# Tach-to-CAN.net
KiCad netlist of a schematic drawn in EAGLE
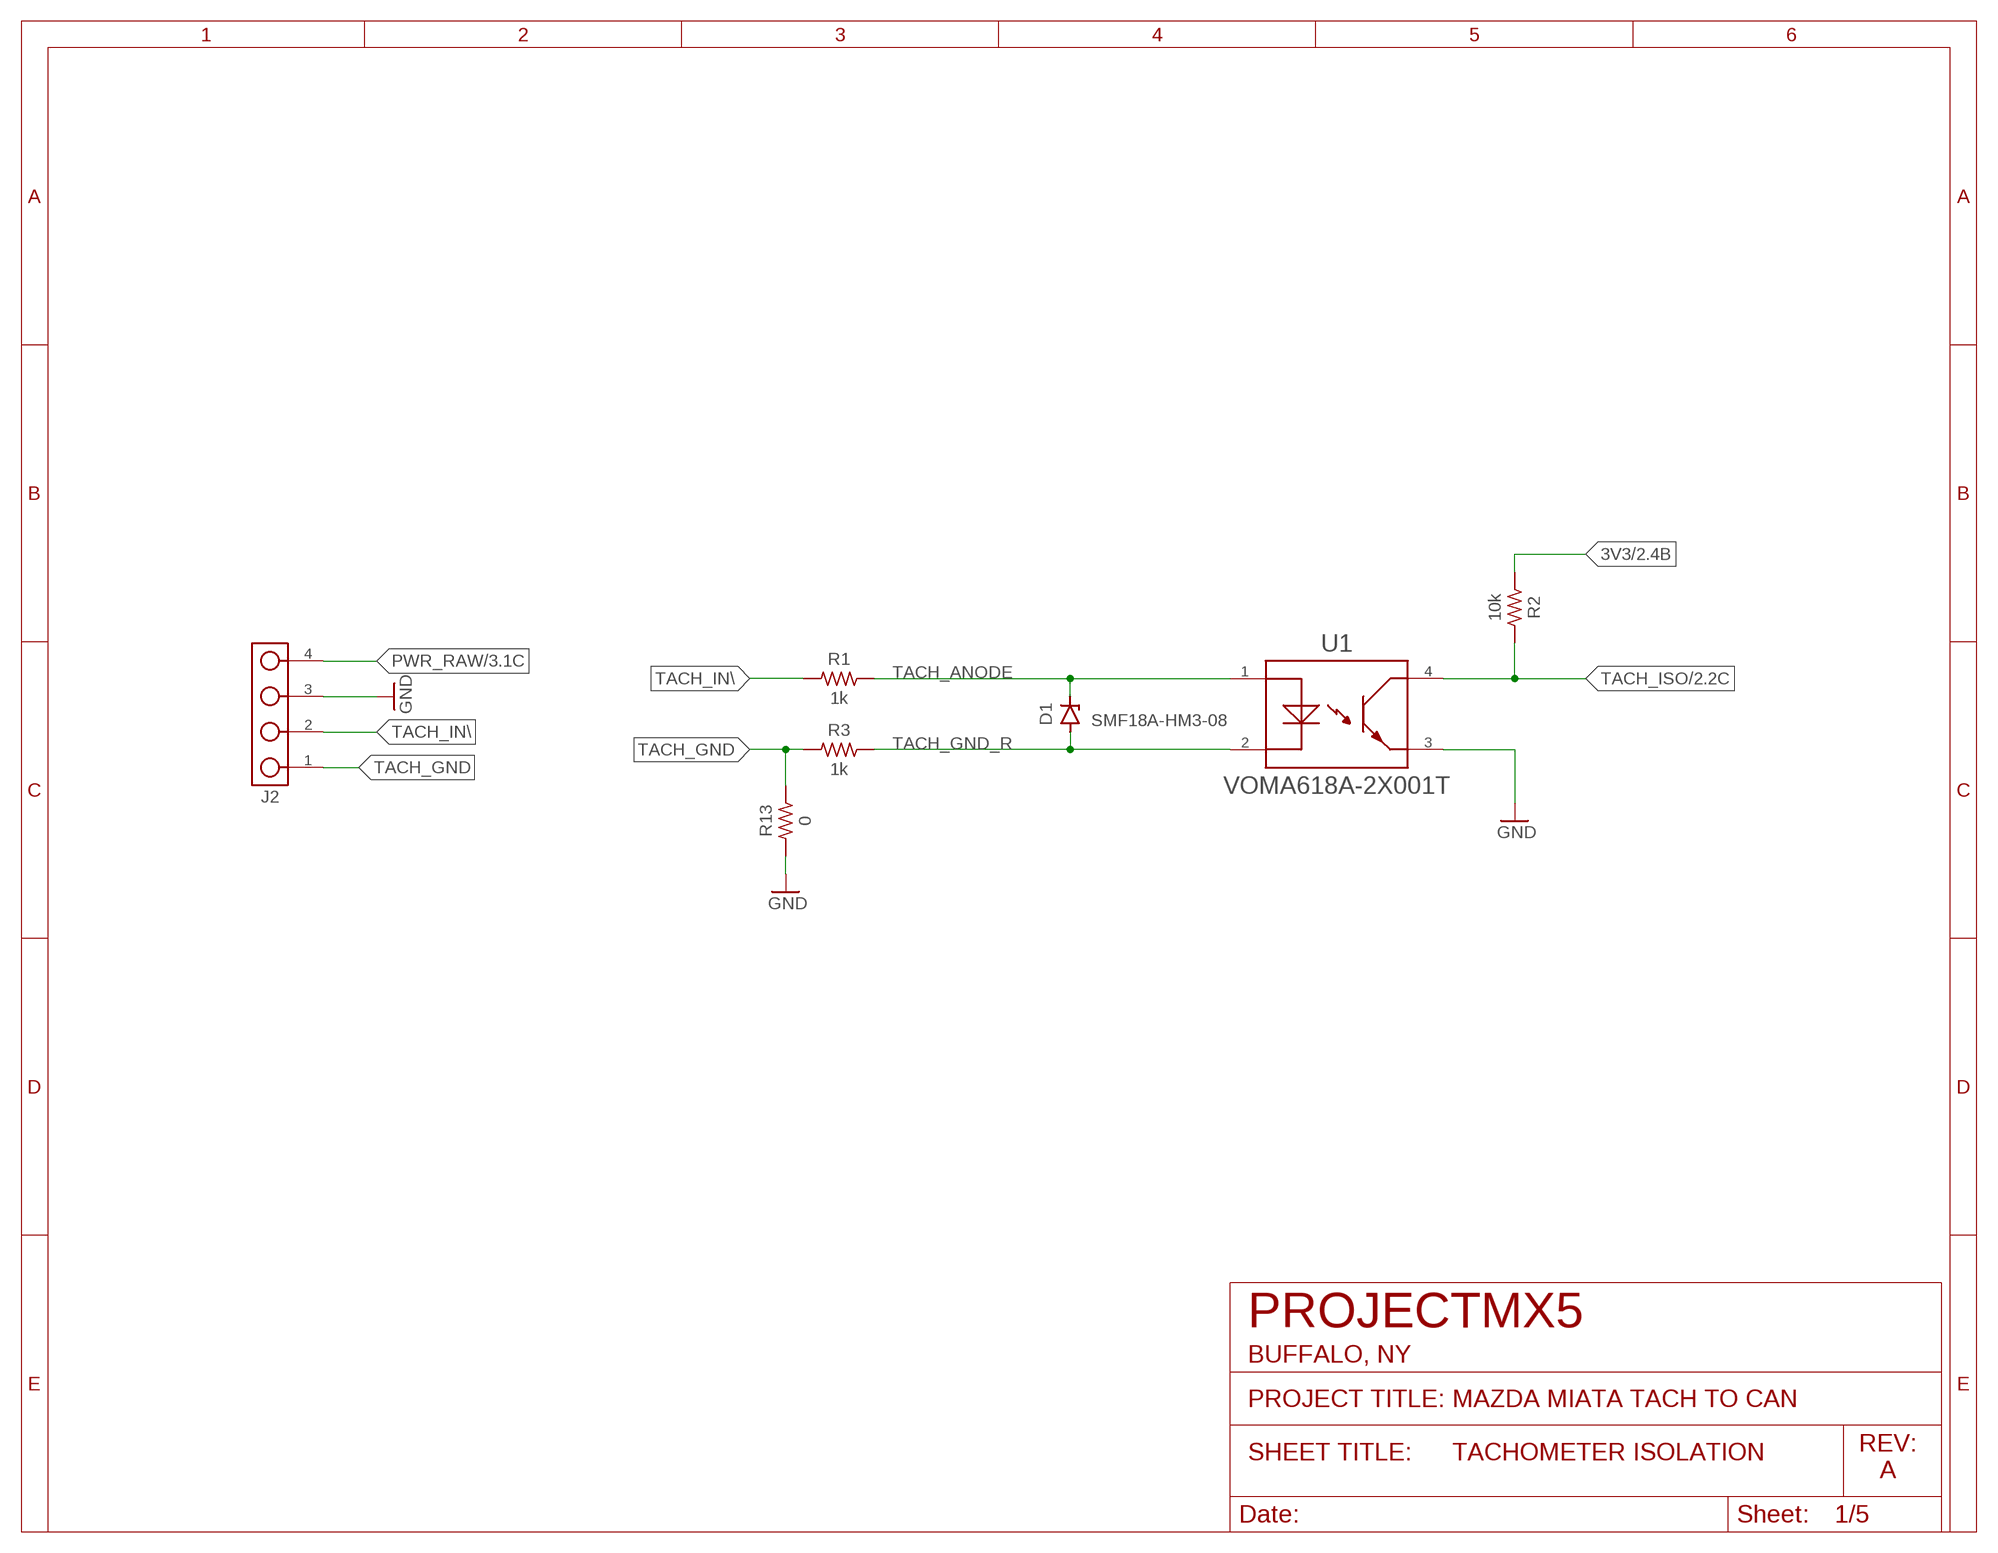
[diagram p0: schematic, sheet 1]
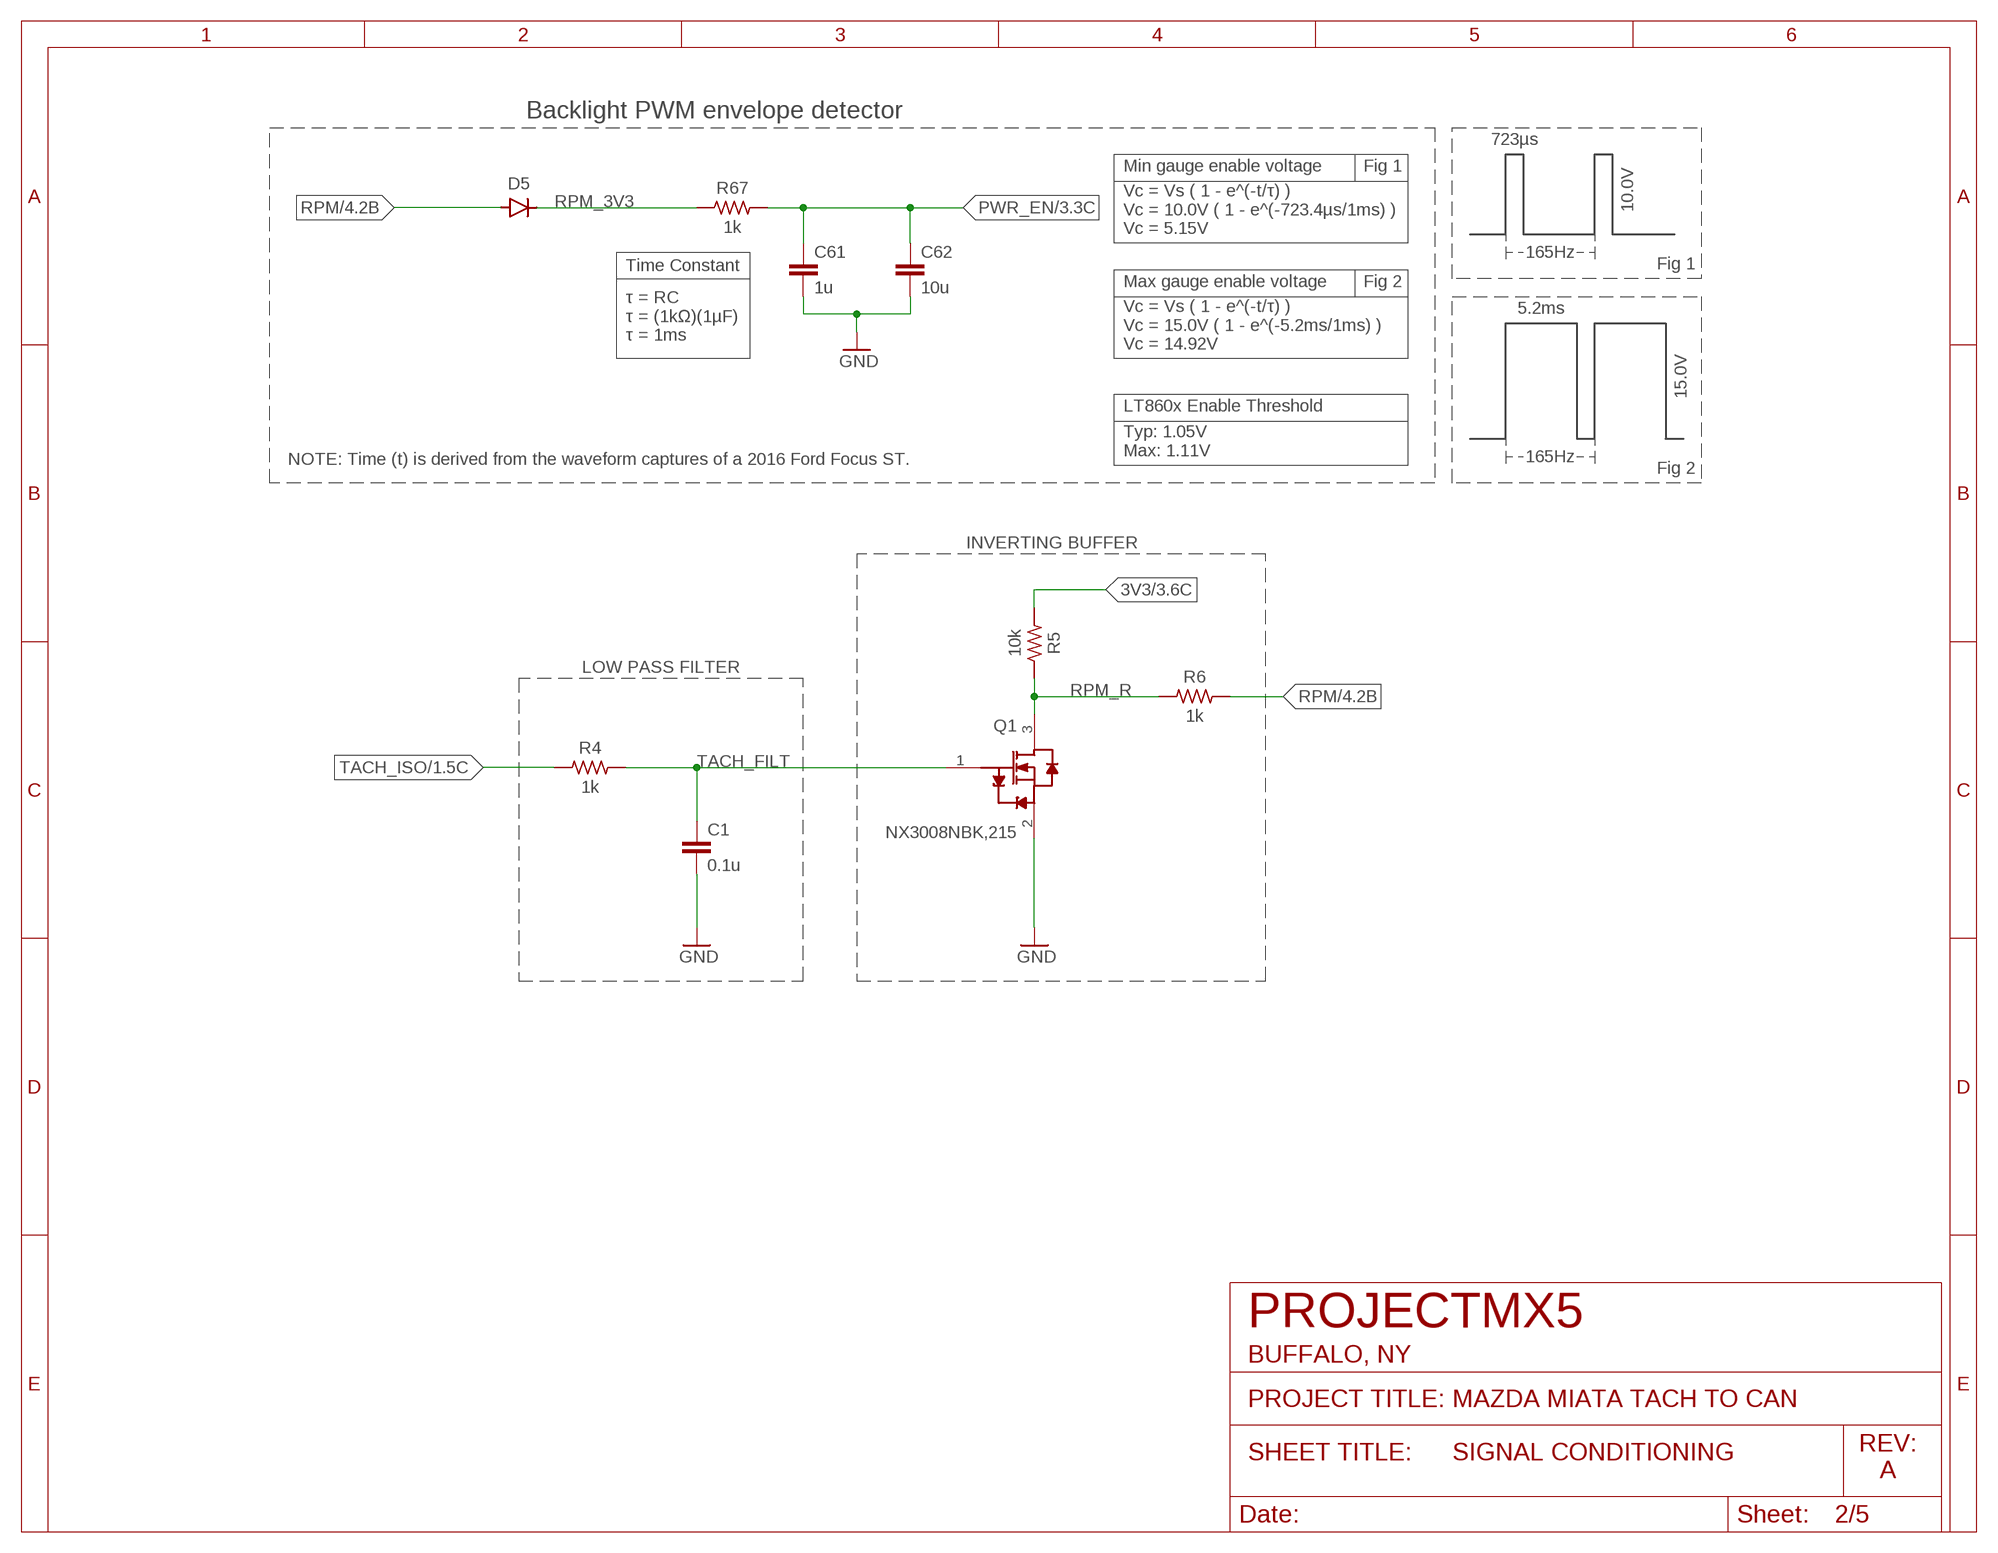
[diagram p1: schematic, sheet 2]
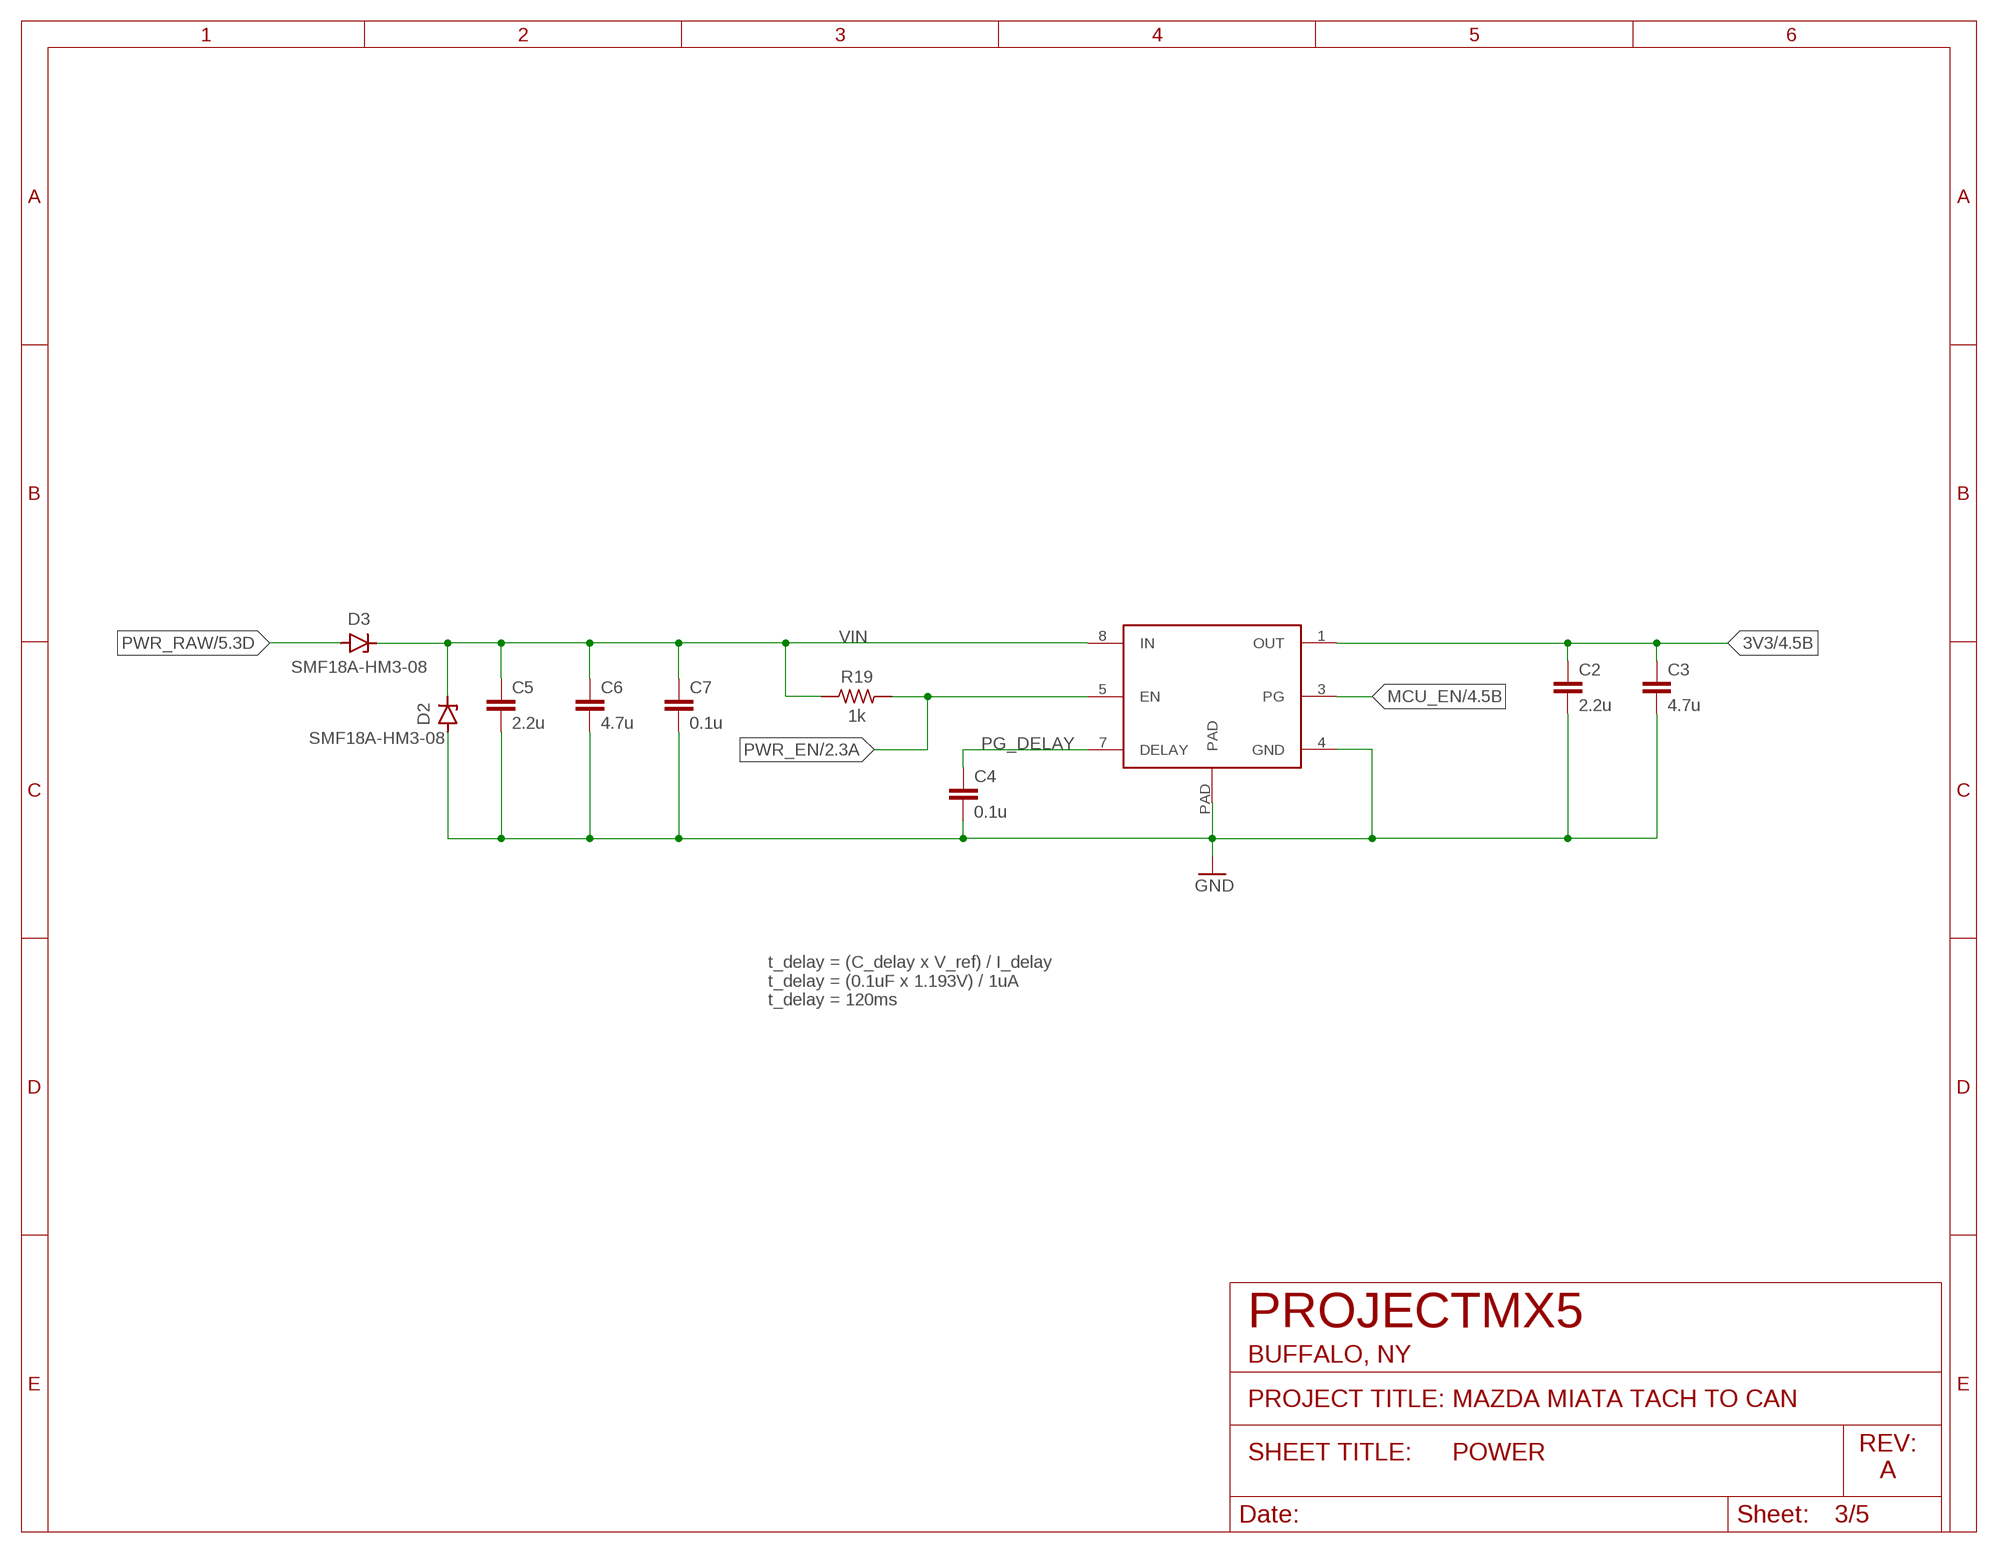
[diagram p2: schematic, sheet 3]
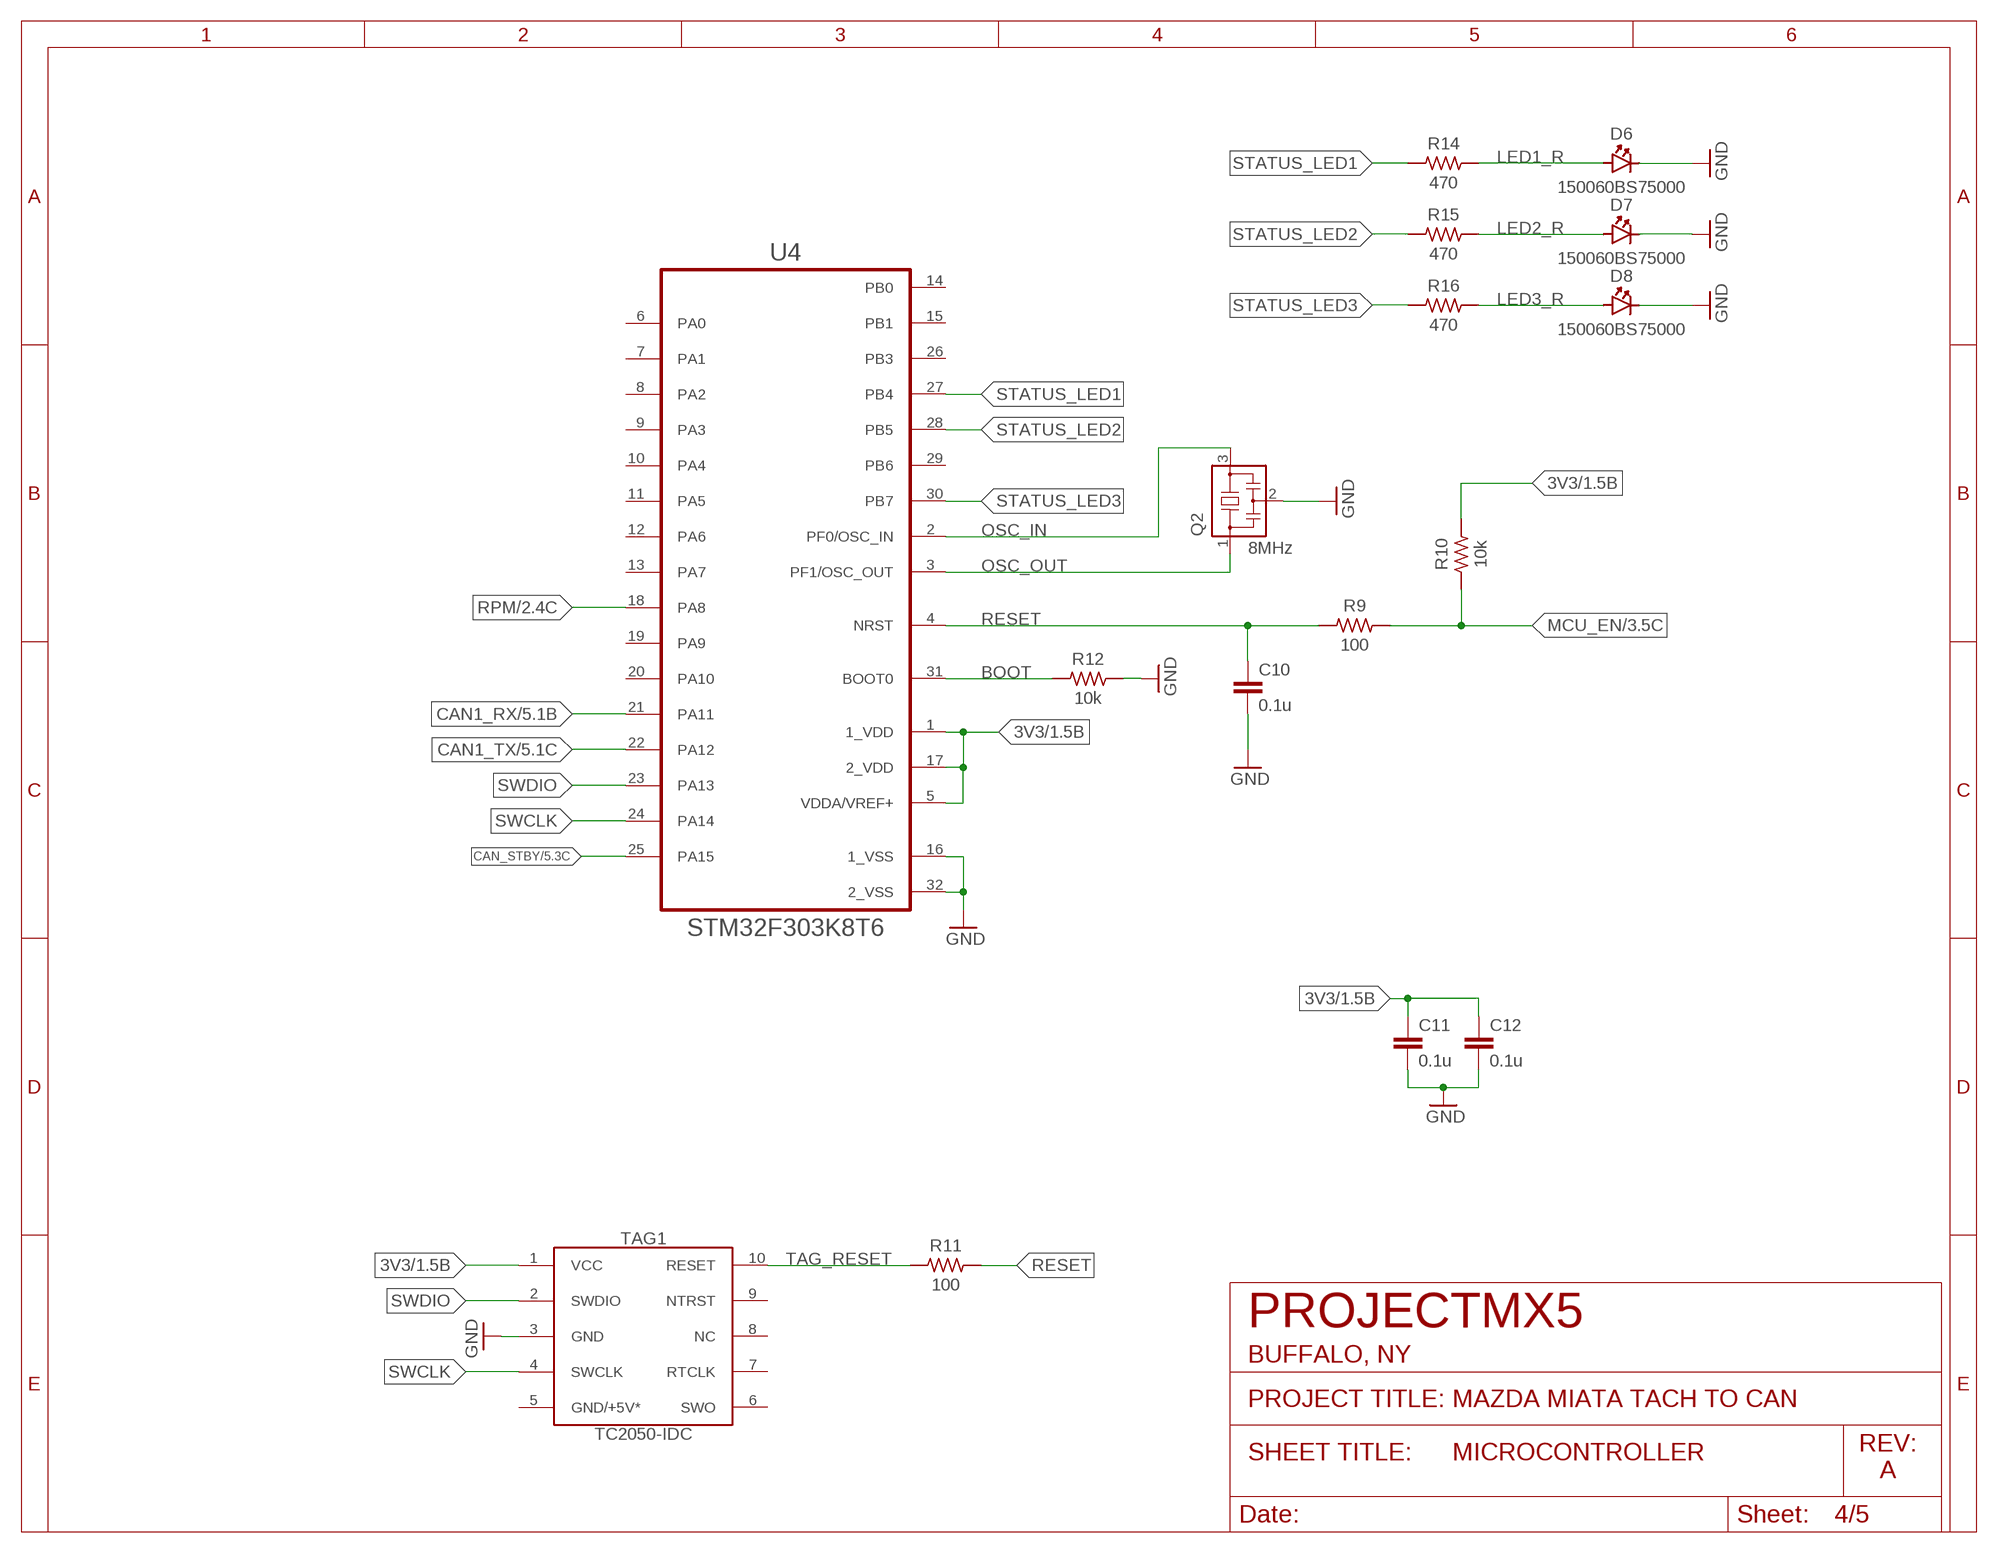
[diagram p3: schematic, sheet 4]
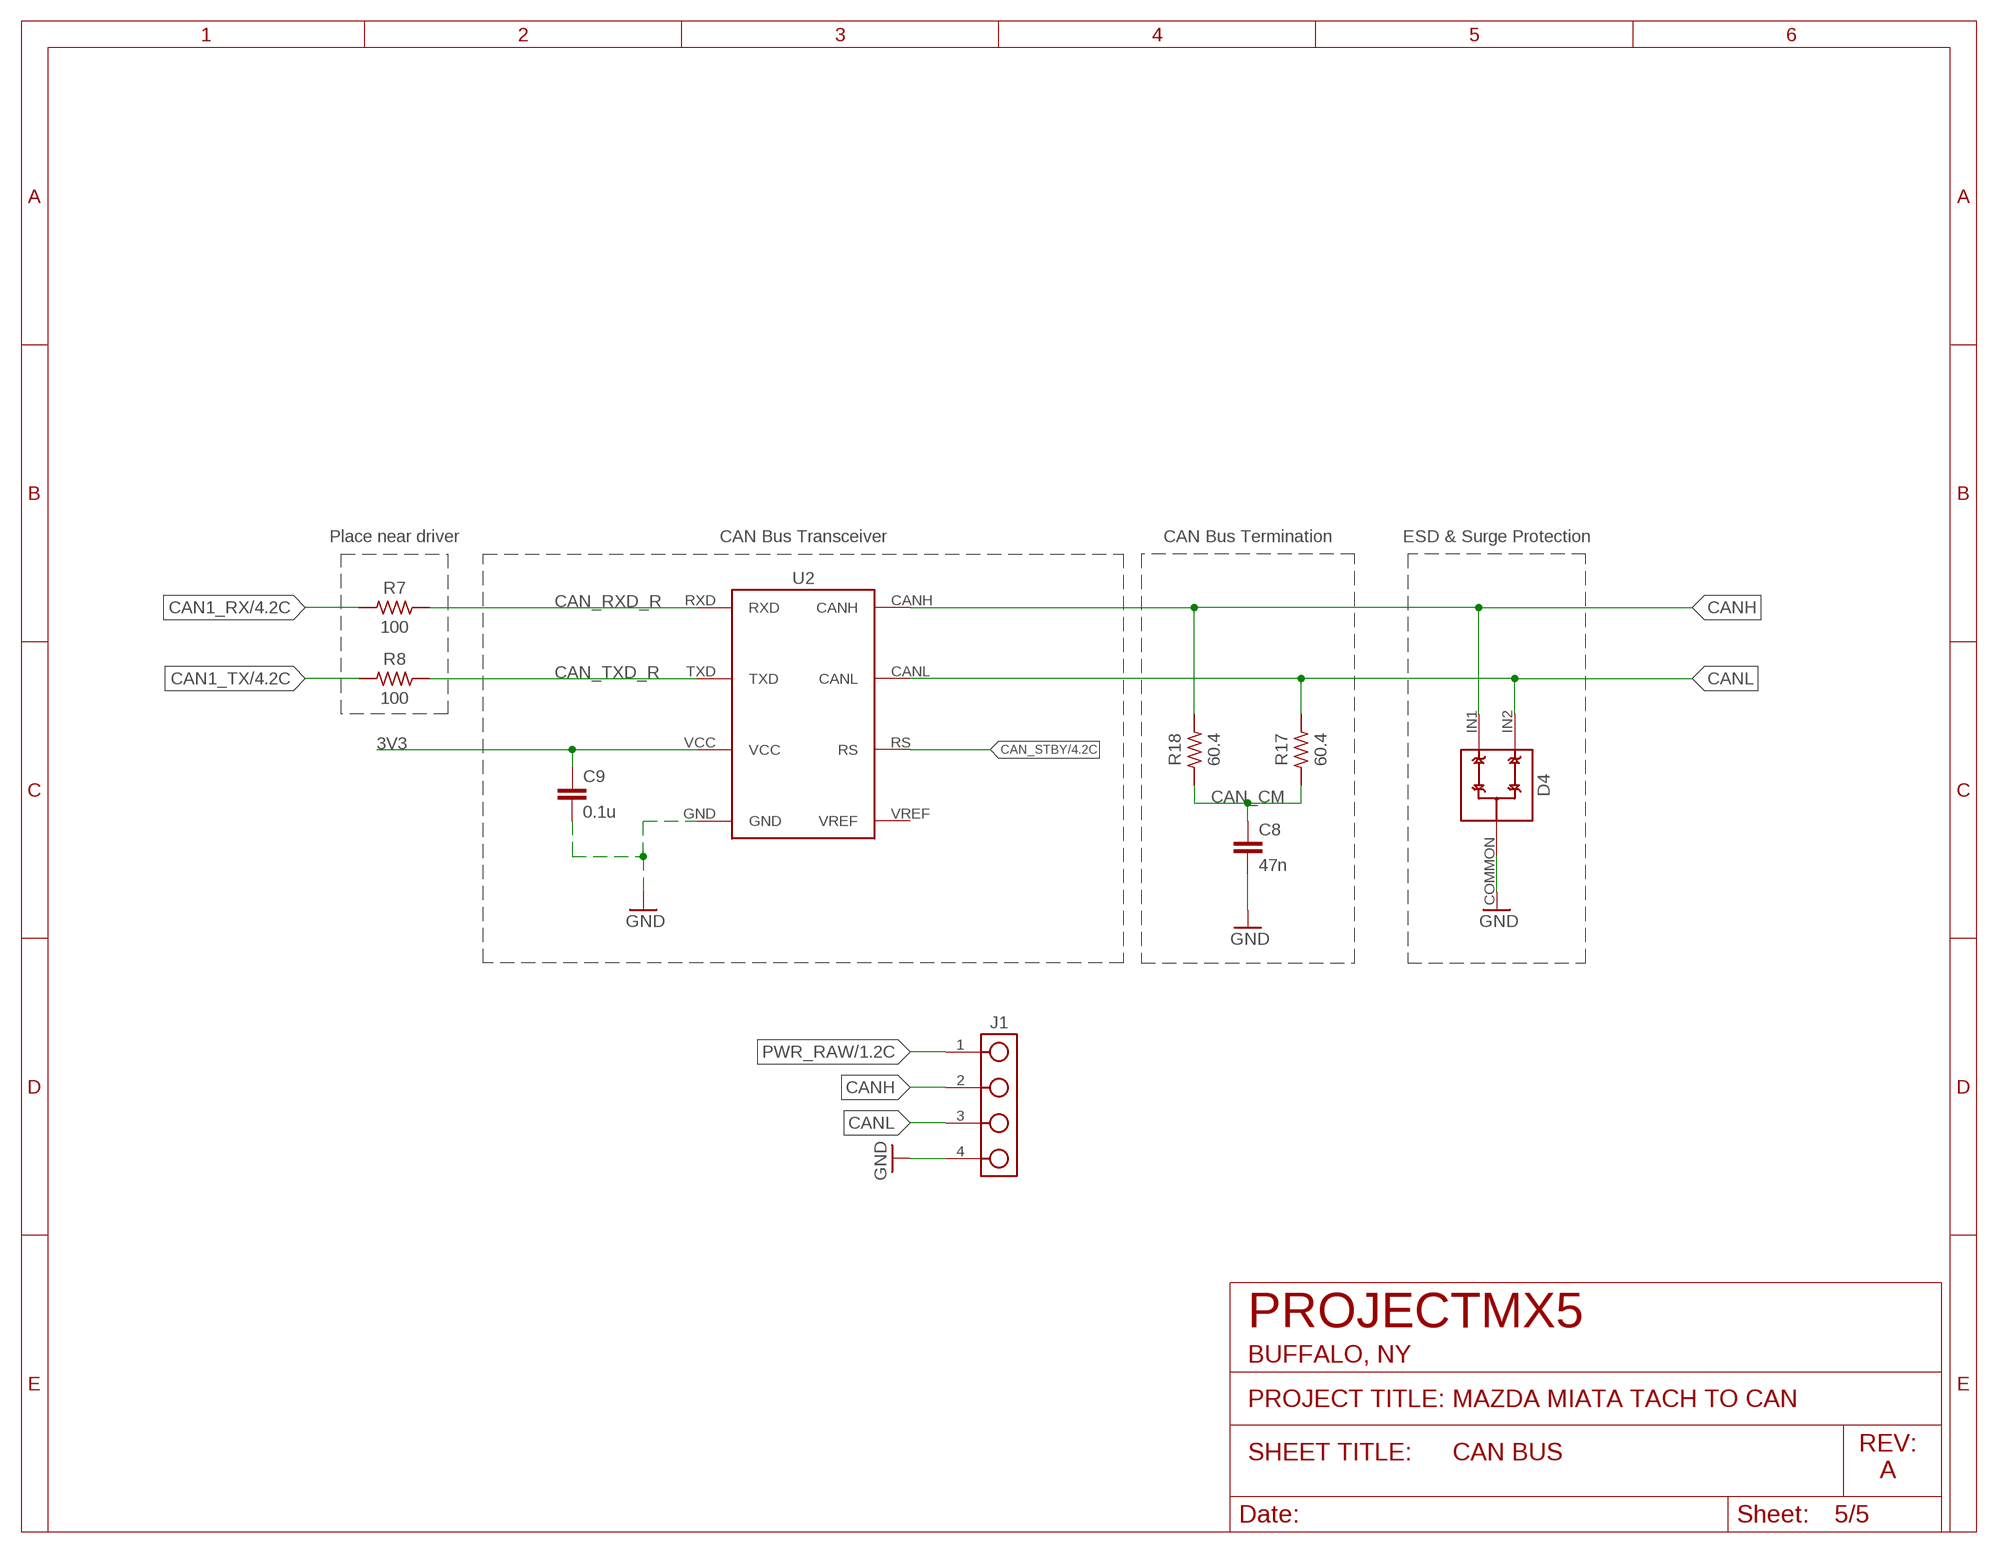
[diagram p4: schematic, sheet 5]

(export (version "E")
  (design (tool "Eeschema 10.0.6"))
  (components
    (comp (ref "C10")
      (value "0.1u")
      (footprint "eagle-import:CAP-0603")
      (fields (field (name "MFG") "KEMET"))
      (libsource (lib "eagle-import") (part "0.1UF-X7R-50V-20%"))
    )
    (comp (ref "C11")
      (value "0.1u")
      (footprint "eagle-import:CAP-0603")
      (fields (field (name "MFG") "KEMET"))
      (libsource (lib "eagle-import") (part "0.1UF-X7R-50V-20%"))
    )
    (comp (ref "C12")
      (value "0.1u")
      (footprint "eagle-import:CAP-0603")
      (fields (field (name "MFG") "KEMET"))
      (libsource (lib "eagle-import") (part "0.1UF-X7R-50V-20%"))
    )
    (comp (ref "D6")
      (value "LED_BLUE_0603_WURTH")
      (footprint "eagle-import:WURTH_0603_LED")
      (fields (field (name "PN") "150060BS75000") (field (name "MFG") "WURTH ELEKTRONIK"))
      (libsource (lib "eagle-import") (part "LED_BLUE_0603_WURTH"))
    )
    (comp (ref "D7")
      (value "LED_BLUE_0603_WURTH")
      (footprint "eagle-import:WURTH_0603_LED")
      (fields (field (name "PN") "150060BS75000") (field (name "MFG") "WURTH ELEKTRONIK"))
      (libsource (lib "eagle-import") (part "LED_BLUE_0603_WURTH"))
    )
    (comp (ref "D8")
      (value "LED_BLUE_0603_WURTH")
      (footprint "eagle-import:WURTH_0603_LED")
      (fields (field (name "PN") "150060BS75000") (field (name "MFG") "WURTH ELEKTRONIK"))
      (libsource (lib "eagle-import") (part "LED_BLUE_0603_WURTH"))
    )
    (comp (ref "Q2")
      (value "8MHz")
      (footprint "eagle-import:CSTCR6M")
      (fields (field (name "MFG") "MURATA"))
      (libsource (lib "eagle-import") (part "CSTNE8M00GH5C000R0"))
    )
    (comp (ref "R9")
      (value "100")
      (footprint "eagle-import:REST-0603")
      (fields (field (name "MFG") "VISHAY"))
      (libsource (lib "eagle-import") (part "100OHM-0603-1%-1/10W"))
    )
    (comp (ref "R10")
      (value "10k")
      (footprint "eagle-import:REST-0603")
      (fields (field (name "MFG") "VISHAY"))
      (libsource (lib "eagle-import") (part "10KOHM-0603-1%-1/10W"))
    )
    (comp (ref "R11")
      (value "100")
      (footprint "eagle-import:REST-0603")
      (fields (field (name "MFG") "VISHAY"))
      (libsource (lib "eagle-import") (part "100OHM-0603-1%-1/10W"))
    )
    (comp (ref "R12")
      (value "10k")
      (footprint "eagle-import:REST-0603")
      (fields (field (name "MFG") "VISHAY"))
      (libsource (lib "eagle-import") (part "10KOHM-0603-1%-1/10W"))
    )
    (comp (ref "R14")
      (value "470")
      (footprint "eagle-import:REST-0603")
      (fields (field (name "MFG") "PANASONIC"))
      (libsource (lib "eagle-import") (part "470OHM-0603-1%-1/10W"))
    )
    (comp (ref "R15")
      (value "470")
      (footprint "eagle-import:REST-0603")
      (fields (field (name "MFG") "PANASONIC"))
      (libsource (lib "eagle-import") (part "470OHM-0603-1%-1/10W"))
    )
    (comp (ref "R16")
      (value "470")
      (footprint "eagle-import:REST-0603")
      (fields (field (name "MFG") "PANASONIC"))
      (libsource (lib "eagle-import") (part "470OHM-0603-1%-1/10W"))
    )
    (comp (ref "TAG1")
      (value "TC2050-IDC")
      (footprint "eagle-import:TC2050-IDC")
      (fields (field (name "PN") "TC2050-IDC") (field (name "MFG") "TAG-CONNECT"))
      (libsource (lib "eagle-import") (part "TC2050-IDC"))
    )
    (comp (ref "U4")
      (value "STM32F303K8T6STMICROELECTRONICS_STM32F303K8T6")
      (footprint "eagle-import:STM32F303K8T6")
      (fields (field (name "PARTNUMBER") "STM32F303K8T6") (field (name "MANUFACTURER") "STMICROELECTRONICS"))
      (libsource (lib "eagle-import") (part "STM32F303K8T6STMICROELECTRONICS_STM32F303K8T6"))
    )
    (comp (ref "C1")
      (value "0.1u")
      (footprint "eagle-import:CAP-0603")
      (fields (field (name "MFG") "KEMET"))
      (libsource (lib "eagle-import") (part "0.1UF-X7R-50V-20%"))
    )
    (comp (ref "C61")
      (value "1u")
      (footprint "eagle-import:CAP-0805")
      (fields (field (name "MFG") "TAIYO YUDEN"))
      (libsource (lib "eagle-import") (part "1UF-X7R-50V-10%"))
    )
    (comp (ref "C62")
      (value "10u")
      (footprint "eagle-import:CAP-1206")
      (fields (field (name "MFG") "TDK"))
      (libsource (lib "eagle-import") (part "10UF-X7R-50V-10%"))
    )
    (comp (ref "D5")
      (value "AVX_SD1206S040S2R0")
      (footprint "eagle-import:AVX_SD1206S040S2R0")
      (fields (field (name "MFG") "AVX"))
      (libsource (lib "eagle-import") (part "AVX_SD1206S040S2R0"))
    )
    (comp (ref "Q1")
      (value "NXP_NX3008NBK,215NXP_SOT23")
      (footprint "eagle-import:NXP_SOT23")
      (fields (field (name "PN") "NX3008NBK,215") (field (name "MFG") "NXP"))
      (libsource (lib "eagle-import") (part "NXP_NX3008NBK,215NXP_SOT23"))
    )
    (comp (ref "R4")
      (value "1k")
      (footprint "eagle-import:REST-0603")
      (fields (field (name "MFG") "VISHAY"))
      (libsource (lib "eagle-import") (part "1KOHM-0603-1%-1/10W"))
    )
    (comp (ref "R5")
      (value "10k")
      (footprint "eagle-import:REST-0603")
      (fields (field (name "MFG") "VISHAY"))
      (libsource (lib "eagle-import") (part "10KOHM-0603-1%-1/10W"))
    )
    (comp (ref "R6")
      (value "1k")
      (footprint "eagle-import:REST-0603")
      (fields (field (name "MFG") "VISHAY"))
      (libsource (lib "eagle-import") (part "1KOHM-0603-1%-1/10W"))
    )
    (comp (ref "R67")
      (value "1k")
      (footprint "eagle-import:REST-0603")
      (fields (field (name "MFG") "VISHAY"))
      (libsource (lib "eagle-import") (part "1KOHM-0603-1%-1/10W"))
    )
    (comp (ref "D1")
      (value "VISHAY_SMF18A-HM3-08")
      (footprint "eagle-import:VISHAY_SMFXXA-HM3-08")
      (fields (field (name "PN") "SMF18A-HM3-08") (field (name "MFG") "VISHAY"))
      (libsource (lib "eagle-import") (part "VISHAY_SMF18A-HM3-08"))
    )
    (comp (ref "J2")
      (value "CONN_4PIN_VERT")
      (footprint "eagle-import:CONN_100MIL_4_PIN")
      (libsource (lib "eagle-import") (part "CONN_4PIN_VERT"))
    )
    (comp (ref "R1")
      (value "1k")
      (footprint "eagle-import:REST-0603")
      (fields (field (name "MFG") "VISHAY"))
      (libsource (lib "eagle-import") (part "1KOHM-0603-1%-1/10W"))
    )
    (comp (ref "R2")
      (value "10k")
      (footprint "eagle-import:REST-0603")
      (fields (field (name "MFG") "VISHAY"))
      (libsource (lib "eagle-import") (part "10KOHM-0603-1%-1/10W"))
    )
    (comp (ref "R3")
      (value "1k")
      (footprint "eagle-import:REST-0603")
      (fields (field (name "MFG") "VISHAY"))
      (libsource (lib "eagle-import") (part "1KOHM-0603-1%-1/10W"))
    )
    (comp (ref "R13")
      (value "0")
      (footprint "eagle-import:REST-0603")
      (fields (field (name "MFG") "VISHAY"))
      (libsource (lib "eagle-import") (part "0OHM-0603-1%-1/10W"))
    )
    (comp (ref "U1")
      (value "VISHAY_VOMA618A-2X001T")
      (footprint "eagle-import:VISHAY_SOP-4")
      (fields
        (field (name "PN") "VOMA618A-2X001T")
        (field (name "MFG") "VISHAY")
        (field (name "SPICEPREFIX") "E")
      )
      (libsource (lib "eagle-import") (part "VISHAY_VOMA618A-2X001T"))
    )
    (comp (ref "C8")
      (value "47n")
      (footprint "eagle-import:CAP-0603")
      (fields (field (name "MFG") "TDK"))
      (libsource (lib "eagle-import") (part "47NF-X7R-50V-10%"))
    )
    (comp (ref "C9")
      (value "0.1u")
      (footprint "eagle-import:CAP-0603")
      (fields (field (name "MFG") "KEMET"))
      (libsource (lib "eagle-import") (part "0.1UF-X7R-50V-20%"))
    )
    (comp (ref "D4")
      (value "CDSOT23-T24CAN-Q")
      (footprint "eagle-import:BOURNS_CDSOT23-T24CAN-Q")
      (fields (field (name "MFG") "BOURNS"))
      (libsource (lib "eagle-import") (part "BOURNS_CDSOT23-T24CAN-Q"))
    )
    (comp (ref "J1")
      (value "CONN_4PIN_VERT")
      (footprint "eagle-import:CONN_100MIL_4_PIN")
      (libsource (lib "eagle-import") (part "CONN_4PIN_VERT"))
    )
    (comp (ref "R7")
      (value "100")
      (footprint "eagle-import:REST-0603")
      (fields (field (name "MFG") "VISHAY"))
      (libsource (lib "eagle-import") (part "100OHM-0603-1%-1/10W"))
    )
    (comp (ref "R8")
      (value "100")
      (footprint "eagle-import:REST-0603")
      (fields (field (name "MFG") "VISHAY"))
      (libsource (lib "eagle-import") (part "100OHM-0603-1%-1/10W"))
    )
    (comp (ref "R17")
      (value "60.4")
      (footprint "eagle-import:REST-0603")
      (fields (field (name "MFG") "KOA"))
      (libsource (lib "eagle-import") (part "60.4OHM-0603-1%-1/10W"))
    )
    (comp (ref "R18")
      (value "60.4")
      (footprint "eagle-import:REST-0603")
      (fields (field (name "MFG") "KOA"))
      (libsource (lib "eagle-import") (part "60.4OHM-0603-1%-1/10W"))
    )
    (comp (ref "U2")
      (value "TI_SN65HVD23X")
      (footprint "eagle-import:TI_SN65HVD23X")
      (fields
        (field (name "PARTNUMBER") " SN65HVD232QDRQ1 ")
        (field (name "MANUFACTURER") "TEXAS INSTRUMENTS")
      )
      (libsource (lib "eagle-import") (part "TI_SN65HVD23X"))
    )
    (comp (ref "C2")
      (value "2.2u")
      (footprint "eagle-import:CAP-0805")
      (fields (field (name "MFG") "AVX"))
      (libsource (lib "eagle-import") (part "2.2UF-X7R-25V-10%"))
    )
    (comp (ref "C3")
      (value "4.7u")
      (footprint "eagle-import:CAP-1206")
      (fields (field (name "MFG") "KEMET"))
      (libsource (lib "eagle-import") (part "4.7UF-X7R-50V-10%"))
    )
    (comp (ref "C4")
      (value "0.1u")
      (footprint "eagle-import:CAP-0603")
      (fields (field (name "MFG") "KEMET"))
      (libsource (lib "eagle-import") (part "0.1UF-X7R-50V-20%"))
    )
    (comp (ref "C5")
      (value "2.2u")
      (footprint "eagle-import:CAP-0805")
      (fields (field (name "MFG") "AVX"))
      (libsource (lib "eagle-import") (part "2.2UF-X7R-25V-10%"))
    )
    (comp (ref "C6")
      (value "4.7u")
      (footprint "eagle-import:CAP-1206")
      (fields (field (name "MFG") "KEMET"))
      (libsource (lib "eagle-import") (part "4.7UF-X7R-50V-10%"))
    )
    (comp (ref "C7")
      (value "0.1u")
      (footprint "eagle-import:CAP-0603")
      (fields (field (name "MFG") "KEMET"))
      (libsource (lib "eagle-import") (part "0.1UF-X7R-50V-20%"))
    )
    (comp (ref "D2")
      (value "VISHAY_SMF18A-HM3-08")
      (footprint "eagle-import:VISHAY_SMFXXA-HM3-08")
      (fields (field (name "PN") "SMF18A-HM3-08") (field (name "MFG") "VISHAY"))
      (libsource (lib "eagle-import") (part "VISHAY_SMF18A-HM3-08"))
    )
    (comp (ref "D3")
      (value "VISHAY_SMF18A-HM3-08")
      (footprint "eagle-import:VISHAY_SMFXXA-HM3-08")
      (fields (field (name "PN") "SMF18A-HM3-08") (field (name "MFG") "VISHAY"))
      (libsource (lib "eagle-import") (part "VISHAY_SMF18A-HM3-08"))
    )
    (comp (ref "R19")
      (value "1k")
      (footprint "eagle-import:REST-0603")
      (fields (field (name "MFG") "VISHAY"))
      (libsource (lib "eagle-import") (part "1KOHM-0603-1%-1/10W"))
    )
    (comp (ref "U3")
      (value "TI_TPS7A1633AQDGNRQ1")
      (footprint "eagle-import:TI_MSSOP8")
      (fields (field (name "MFG") "TI"))
      (libsource (lib "eagle-import") (part "TI_TPS7A1633AQDGNRQ1"))
    )
  )
  (nets
    (net (code "1") (name "3V3") (class "Default")
      (node (ref "C11") (pin "1") (pinfunction "1_1") (pintype "passive"))
      (node (ref "C12") (pin "1") (pinfunction "1_1") (pintype "passive"))
      (node (ref "C2") (pin "1") (pinfunction "1_1") (pintype "passive"))
      (node (ref "C3") (pin "1") (pinfunction "1_1") (pintype "passive"))
      (node (ref "C9") (pin "1") (pinfunction "1_1") (pintype "passive"))
      (node (ref "R10") (pin "2") (pinfunction "2_2") (pintype "bidirectional"))
      (node (ref "R2") (pin "1") (pinfunction "1_1") (pintype "bidirectional"))
      (node (ref "R5") (pin "1") (pinfunction "1_1") (pintype "bidirectional"))
      (node (ref "TAG1") (pin "1") (pinfunction "VCC_1") (pintype "passive"))
      (node (ref "U2") (pin "VCC") (pinfunction "VCC_VCC") (pintype "bidirectional"))
      (node (ref "U3") (pin "1") (pinfunction "OUT_1") (pintype "bidirectional"))
      (node (ref "U4") (pin "1") (pinfunction "1_VDD_1") (pintype "power_in"))
      (node (ref "U4") (pin "17") (pinfunction "2_VDD_17") (pintype "power_in"))
      (node (ref "U4") (pin "5") (pinfunction "VDDA/VREF+_5") (pintype "power_in"))
    )
    (net (code "2") (name "BOOT") (class "Default")
      (node (ref "R12") (pin "1") (pinfunction "1_1") (pintype "bidirectional"))
      (node (ref "U4") (pin "31") (pinfunction "BOOT0_31") (pintype "input"))
    )
    (net (code "3") (name "CAN1_RX") (class "Default")
      (node (ref "R7") (pin "1") (pinfunction "1_1") (pintype "bidirectional"))
      (node (ref "U4") (pin "21") (pinfunction "PA11_21") (pintype "bidirectional"))
    )
    (net (code "4") (name "CAN1_TX") (class "Default")
      (node (ref "R8") (pin "1") (pinfunction "1_1") (pintype "bidirectional"))
      (node (ref "U4") (pin "22") (pinfunction "PA12_22") (pintype "bidirectional"))
    )
    (net (code "5") (name "CANH") (class "Default")
      (node (ref "D4") (pin "IN1") (pinfunction "IN2_IN1") (pintype "bidirectional"))
      (node (ref "J1") (pin "2") (pinfunction "2_2") (pintype "bidirectional"))
      (node (ref "R18") (pin "2") (pinfunction "2_2") (pintype "bidirectional"))
      (node (ref "U2") (pin "CANH") (pinfunction "CANH_CANH") (pintype "bidirectional"))
    )
    (net (code "6") (name "CANL") (class "Default")
      (node (ref "D4") (pin "IN2") (pinfunction "IN1_IN2") (pintype "bidirectional"))
      (node (ref "J1") (pin "3") (pinfunction "3_3") (pintype "bidirectional"))
      (node (ref "R17") (pin "2") (pinfunction "2_2") (pintype "bidirectional"))
      (node (ref "U2") (pin "CANL") (pinfunction "CANL_CANL") (pintype "bidirectional"))
    )
    (net (code "7") (name "CAN_CM") (class "Default")
      (node (ref "C8") (pin "1") (pinfunction "1_1") (pintype "passive"))
      (node (ref "R17") (pin "1") (pinfunction "1_1") (pintype "bidirectional"))
      (node (ref "R18") (pin "1") (pinfunction "1_1") (pintype "bidirectional"))
    )
    (net (code "8") (name "CAN_RXD_R") (class "Default")
      (node (ref "R7") (pin "2") (pinfunction "2_2") (pintype "bidirectional"))
      (node (ref "U2") (pin "RXD") (pinfunction "RXD_RXD") (pintype "output"))
    )
    (net (code "9") (name "CAN_STBY") (class "Default")
      (node (ref "U2") (pin "RS") (pinfunction "RS_RS") (pintype "input"))
      (node (ref "U4") (pin "25") (pinfunction "PA15_25") (pintype "bidirectional"))
    )
    (net (code "10") (name "CAN_TXD_R") (class "Default")
      (node (ref "R8") (pin "2") (pinfunction "2_2") (pintype "bidirectional"))
      (node (ref "U2") (pin "TXD") (pinfunction "TXD_TXD") (pintype "input"))
    )
    (net (code "11") (name "GND") (class "Default")
      (node (ref "C1") (pin "2") (pinfunction "2_2") (pintype "passive"))
      (node (ref "C10") (pin "2") (pinfunction "2_2") (pintype "passive"))
      (node (ref "C11") (pin "2") (pinfunction "2_2") (pintype "passive"))
      (node (ref "C12") (pin "2") (pinfunction "2_2") (pintype "passive"))
      (node (ref "C2") (pin "2") (pinfunction "2_2") (pintype "passive"))
      (node (ref "C3") (pin "2") (pinfunction "2_2") (pintype "passive"))
      (node (ref "C4") (pin "2") (pinfunction "2_2") (pintype "passive"))
      (node (ref "C5") (pin "2") (pinfunction "2_2") (pintype "passive"))
      (node (ref "C6") (pin "2") (pinfunction "2_2") (pintype "passive"))
      (node (ref "C61") (pin "2") (pinfunction "2_2") (pintype "passive"))
      (node (ref "C62") (pin "2") (pinfunction "2_2") (pintype "passive"))
      (node (ref "C7") (pin "2") (pinfunction "2_2") (pintype "passive"))
      (node (ref "C8") (pin "2") (pinfunction "2_2") (pintype "passive"))
      (node (ref "C9") (pin "2") (pinfunction "2_2") (pintype "passive"))
      (node (ref "D2") (pin "A") (pinfunction "A_A") (pintype "passive"))
      (node (ref "D4") (pin "COMMON") (pinfunction "OUT_COMMON") (pintype "bidirectional"))
      (node (ref "D6") (pin "C") (pinfunction "C_C") (pintype "passive"))
      (node (ref "D7") (pin "C") (pinfunction "C_C") (pintype "passive"))
      (node (ref "D8") (pin "C") (pinfunction "C_C") (pintype "passive"))
      (node (ref "J1") (pin "4") (pinfunction "4_4") (pintype "bidirectional"))
      (node (ref "J2") (pin "3") (pinfunction "3_3") (pintype "bidirectional"))
      (node (ref "Q1") (pin "2") (pinfunction "S_2") (pintype "passive"))
      (node (ref "Q2") (pin "2") (pinfunction "2_2") (pintype "passive"))
      (node (ref "R12") (pin "2") (pinfunction "2_2") (pintype "bidirectional"))
      (node (ref "R13") (pin "1") (pinfunction "1_1") (pintype "bidirectional"))
      (node (ref "TAG1") (pin "3") (pinfunction "GND_3") (pintype "passive"))
      (node (ref "U1") (pin "3") (pinfunction "3_3") (pintype "bidirectional"))
      (node (ref "U2") (pin "GND") (pinfunction "GND_GND") (pintype "bidirectional"))
      (node (ref "U3") (pin "4") (pinfunction "GND_4") (pintype "bidirectional"))
      (node (ref "U3") (pin "PAD") (pinfunction "PAD_PAD") (pintype "bidirectional"))
      (node (ref "U4") (pin "16") (pinfunction "1_VSS_16") (pintype "power_in"))
      (node (ref "U4") (pin "32") (pinfunction "2_VSS_32") (pintype "power_in"))
    )
    (net (code "12") (name "LED1_R") (class "Default")
      (node (ref "D6") (pin "A") (pinfunction "A_A") (pintype "passive"))
      (node (ref "R14") (pin "2") (pinfunction "2_2") (pintype "bidirectional"))
    )
    (net (code "13") (name "LED2_R") (class "Default")
      (node (ref "D7") (pin "A") (pinfunction "A_A") (pintype "passive"))
      (node (ref "R15") (pin "2") (pinfunction "2_2") (pintype "bidirectional"))
    )
    (net (code "14") (name "LED3_R") (class "Default")
      (node (ref "D8") (pin "A") (pinfunction "A_A") (pintype "passive"))
      (node (ref "R16") (pin "2") (pinfunction "2_2") (pintype "bidirectional"))
    )
    (net (code "15") (name "MCU_EN") (class "Default")
      (node (ref "R10") (pin "1") (pinfunction "1_1") (pintype "bidirectional"))
      (node (ref "R9") (pin "2") (pinfunction "2_2") (pintype "bidirectional"))
      (node (ref "U3") (pin "3") (pinfunction "PG_3") (pintype "bidirectional"))
    )
    (net (code "16") (name "OSC_IN") (class "Default")
      (node (ref "Q2") (pin "3") (pinfunction "3_3") (pintype "passive"))
      (node (ref "U4") (pin "2") (pinfunction "PF0/OSC_IN_2") (pintype "bidirectional"))
    )
    (net (code "17") (name "OSC_OUT") (class "Default")
      (node (ref "Q2") (pin "1") (pinfunction "1_1") (pintype "passive"))
      (node (ref "U4") (pin "3") (pinfunction "PF1/OSC_OUT_3") (pintype "bidirectional"))
    )
    (net (code "18") (name "PG_DELAY") (class "Default")
      (node (ref "C4") (pin "1") (pinfunction "1_1") (pintype "passive"))
      (node (ref "U3") (pin "7") (pinfunction "DELAY_7") (pintype "bidirectional"))
    )
    (net (code "19") (name "PWR_EN") (class "Default")
      (node (ref "C61") (pin "1") (pinfunction "1_1") (pintype "passive"))
      (node (ref "C62") (pin "1") (pinfunction "1_1") (pintype "passive"))
      (node (ref "R19") (pin "2") (pinfunction "2_2") (pintype "bidirectional"))
      (node (ref "R67") (pin "2") (pinfunction "2_2") (pintype "bidirectional"))
      (node (ref "U3") (pin "5") (pinfunction "EN_5") (pintype "bidirectional"))
    )
    (net (code "20") (name "PWR_RAW") (class "Default")
      (node (ref "D3") (pin "A") (pinfunction "A_A") (pintype "passive"))
      (node (ref "J1") (pin "1") (pinfunction "1_1") (pintype "bidirectional"))
      (node (ref "J2") (pin "4") (pinfunction "4_4") (pintype "bidirectional"))
    )
    (net (code "21") (name "RESET") (class "Default")
      (node (ref "C10") (pin "1") (pinfunction "1_1") (pintype "passive"))
      (node (ref "R11") (pin "2") (pinfunction "2_2") (pintype "bidirectional"))
      (node (ref "R9") (pin "1") (pinfunction "1_1") (pintype "bidirectional"))
      (node (ref "U4") (pin "4") (pinfunction "NRST_4") (pintype "bidirectional"))
    )
    (net (code "22") (name "RPM") (class "Default")
      (node (ref "D5") (pin "A") (pinfunction "A_A") (pintype "passive"))
      (node (ref "R6") (pin "2") (pinfunction "2_2") (pintype "bidirectional"))
      (node (ref "U4") (pin "18") (pinfunction "PA8_18") (pintype "bidirectional"))
    )
    (net (code "23") (name "RPM_3V3") (class "Default")
      (node (ref "D5") (pin "C") (pinfunction "C_C") (pintype "passive"))
      (node (ref "R67") (pin "1") (pinfunction "1_1") (pintype "bidirectional"))
    )
    (net (code "24") (name "RPM_R") (class "Default")
      (node (ref "Q1") (pin "3") (pinfunction "D_3") (pintype "passive"))
      (node (ref "R5") (pin "2") (pinfunction "2_2") (pintype "bidirectional"))
      (node (ref "R6") (pin "1") (pinfunction "1_1") (pintype "bidirectional"))
    )
    (net (code "25") (name "STATUS_LED1") (class "Default")
      (node (ref "R14") (pin "1") (pinfunction "1_1") (pintype "bidirectional"))
      (node (ref "U4") (pin "27") (pinfunction "PB4_27") (pintype "bidirectional"))
    )
    (net (code "26") (name "STATUS_LED2") (class "Default")
      (node (ref "R15") (pin "1") (pinfunction "1_1") (pintype "bidirectional"))
      (node (ref "U4") (pin "28") (pinfunction "PB5_28") (pintype "bidirectional"))
    )
    (net (code "27") (name "STATUS_LED3") (class "Default")
      (node (ref "R16") (pin "1") (pinfunction "1_1") (pintype "bidirectional"))
      (node (ref "U4") (pin "30") (pinfunction "PB7_30") (pintype "bidirectional"))
    )
    (net (code "28") (name "SWCLK") (class "Default")
      (node (ref "TAG1") (pin "4") (pinfunction "SWCLK_4") (pintype "output"))
      (node (ref "U4") (pin "24") (pinfunction "PA14_24") (pintype "bidirectional"))
    )
    (net (code "29") (name "SWDIO") (class "Default")
      (node (ref "TAG1") (pin "2") (pinfunction "SWDIO_2") (pintype "bidirectional"))
      (node (ref "U4") (pin "23") (pinfunction "PA13_23") (pintype "bidirectional"))
    )
    (net (code "30") (name "TACH_ANODE") (class "Default")
      (node (ref "D1") (pin "C") (pinfunction "C_C") (pintype "passive"))
      (node (ref "R1") (pin "2") (pinfunction "2_2") (pintype "bidirectional"))
      (node (ref "U1") (pin "1") (pinfunction "1_1") (pintype "bidirectional"))
    )
    (net (code "31") (name "TACH_FILT") (class "Default")
      (node (ref "C1") (pin "1") (pinfunction "1_1") (pintype "passive"))
      (node (ref "Q1") (pin "1") (pinfunction "G_1") (pintype "passive"))
      (node (ref "R4") (pin "2") (pinfunction "2_2") (pintype "bidirectional"))
    )
    (net (code "32") (name "TACH_GND") (class "Default")
      (node (ref "J2") (pin "1") (pinfunction "1_1") (pintype "bidirectional"))
      (node (ref "R13") (pin "2") (pinfunction "2_2") (pintype "bidirectional"))
      (node (ref "R3") (pin "1") (pinfunction "1_1") (pintype "bidirectional"))
    )
    (net (code "33") (name "TACH_GND_R") (class "Default")
      (node (ref "D1") (pin "A") (pinfunction "A_A") (pintype "passive"))
      (node (ref "R3") (pin "2") (pinfunction "2_2") (pintype "bidirectional"))
      (node (ref "U1") (pin "2") (pinfunction "2_2") (pintype "bidirectional"))
    )
    (net (code "34") (name "TACH_IN\\") (class "Default")
      (node (ref "J2") (pin "2") (pinfunction "2_2") (pintype "bidirectional"))
      (node (ref "R1") (pin "1") (pinfunction "1_1") (pintype "bidirectional"))
    )
    (net (code "35") (name "TACH_ISO") (class "Default")
      (node (ref "R2") (pin "2") (pinfunction "2_2") (pintype "bidirectional"))
      (node (ref "R4") (pin "1") (pinfunction "1_1") (pintype "bidirectional"))
      (node (ref "U1") (pin "4") (pinfunction "4_4") (pintype "bidirectional"))
    )
    (net (code "36") (name "TAG_RESET") (class "Default")
      (node (ref "R11") (pin "1") (pinfunction "1_1") (pintype "bidirectional"))
      (node (ref "TAG1") (pin "10") (pinfunction "RESET_10") (pintype "bidirectional"))
    )
    (net (code "37") (name "VIN") (class "Default")
      (node (ref "C5") (pin "1") (pinfunction "1_1") (pintype "passive"))
      (node (ref "C6") (pin "1") (pinfunction "1_1") (pintype "passive"))
      (node (ref "C7") (pin "1") (pinfunction "1_1") (pintype "passive"))
      (node (ref "D2") (pin "C") (pinfunction "C_C") (pintype "passive"))
      (node (ref "D3") (pin "C") (pinfunction "C_C") (pintype "passive"))
      (node (ref "R19") (pin "1") (pinfunction "1_1") (pintype "bidirectional"))
      (node (ref "U3") (pin "8") (pinfunction "IN_8") (pintype "bidirectional"))
    )
    (net (code "38") (name "unconnected-(TAG1-GND{slash}+5V*-Pad5)") (class "Default")
      (node (ref "TAG1") (pin "5") (pinfunction "GND/+5V*_5") (pintype "passive"))
    )
    (net (code "39") (name "unconnected-(TAG1-NC-Pad8)") (class "Default")
      (node (ref "TAG1") (pin "8") (pinfunction "NC_8") (pintype "no_connect"))
    )
    (net (code "40") (name "unconnected-(TAG1-NTRST-Pad9)") (class "Default")
      (node (ref "TAG1") (pin "9") (pinfunction "NTRST_9") (pintype "bidirectional"))
    )
    (net (code "41") (name "unconnected-(TAG1-RTCLK-Pad7)") (class "Default")
      (node (ref "TAG1") (pin "7") (pinfunction "RTCLK_7") (pintype "bidirectional"))
    )
    (net (code "42") (name "unconnected-(TAG1-SWO-Pad6)") (class "Default")
      (node (ref "TAG1") (pin "6") (pinfunction "SWO_6") (pintype "bidirectional"))
    )
    (net (code "43") (name "unconnected-(U2-PadVREF)") (class "Default")
      (node (ref "U2") (pin "VREF") (pinfunction "VREF_VREF") (pintype "output"))
    )
    (net (code "44") (name "unconnected-(U4-PA0-Pad6)") (class "Default")
      (node (ref "U4") (pin "6") (pinfunction "PA0_6") (pintype "bidirectional"))
    )
    (net (code "45") (name "unconnected-(U4-PA1-Pad7)") (class "Default")
      (node (ref "U4") (pin "7") (pinfunction "PA1_7") (pintype "bidirectional"))
    )
    (net (code "46") (name "unconnected-(U4-PA2-Pad8)") (class "Default")
      (node (ref "U4") (pin "8") (pinfunction "PA2_8") (pintype "bidirectional"))
    )
    (net (code "47") (name "unconnected-(U4-PA3-Pad9)") (class "Default")
      (node (ref "U4") (pin "9") (pinfunction "PA3_9") (pintype "bidirectional"))
    )
    (net (code "48") (name "unconnected-(U4-PA4-Pad10)") (class "Default")
      (node (ref "U4") (pin "10") (pinfunction "PA4_10") (pintype "bidirectional"))
    )
    (net (code "49") (name "unconnected-(U4-PA5-Pad11)") (class "Default")
      (node (ref "U4") (pin "11") (pinfunction "PA5_11") (pintype "bidirectional"))
    )
    (net (code "50") (name "unconnected-(U4-PA6-Pad12)") (class "Default")
      (node (ref "U4") (pin "12") (pinfunction "PA6_12") (pintype "bidirectional"))
    )
    (net (code "51") (name "unconnected-(U4-PA7-Pad13)") (class "Default")
      (node (ref "U4") (pin "13") (pinfunction "PA7_13") (pintype "bidirectional"))
    )
    (net (code "52") (name "unconnected-(U4-PA9-Pad19)") (class "Default")
      (node (ref "U4") (pin "19") (pinfunction "PA9_19") (pintype "bidirectional"))
    )
    (net (code "53") (name "unconnected-(U4-PA10-Pad20)") (class "Default")
      (node (ref "U4") (pin "20") (pinfunction "PA10_20") (pintype "bidirectional"))
    )
    (net (code "54") (name "unconnected-(U4-PB0-Pad14)") (class "Default")
      (node (ref "U4") (pin "14") (pinfunction "PB0_14") (pintype "bidirectional"))
    )
    (net (code "55") (name "unconnected-(U4-PB1-Pad15)") (class "Default")
      (node (ref "U4") (pin "15") (pinfunction "PB1_15") (pintype "bidirectional"))
    )
    (net (code "56") (name "unconnected-(U4-PB3-Pad26)") (class "Default")
      (node (ref "U4") (pin "26") (pinfunction "PB3_26") (pintype "bidirectional"))
    )
    (net (code "57") (name "unconnected-(U4-PB6-Pad29)") (class "Default")
      (node (ref "U4") (pin "29") (pinfunction "PB6_29") (pintype "bidirectional"))
    )
  )
)
